# MIXR_UI.net
KiCad netlist of a schematic drawn in Altium Designer
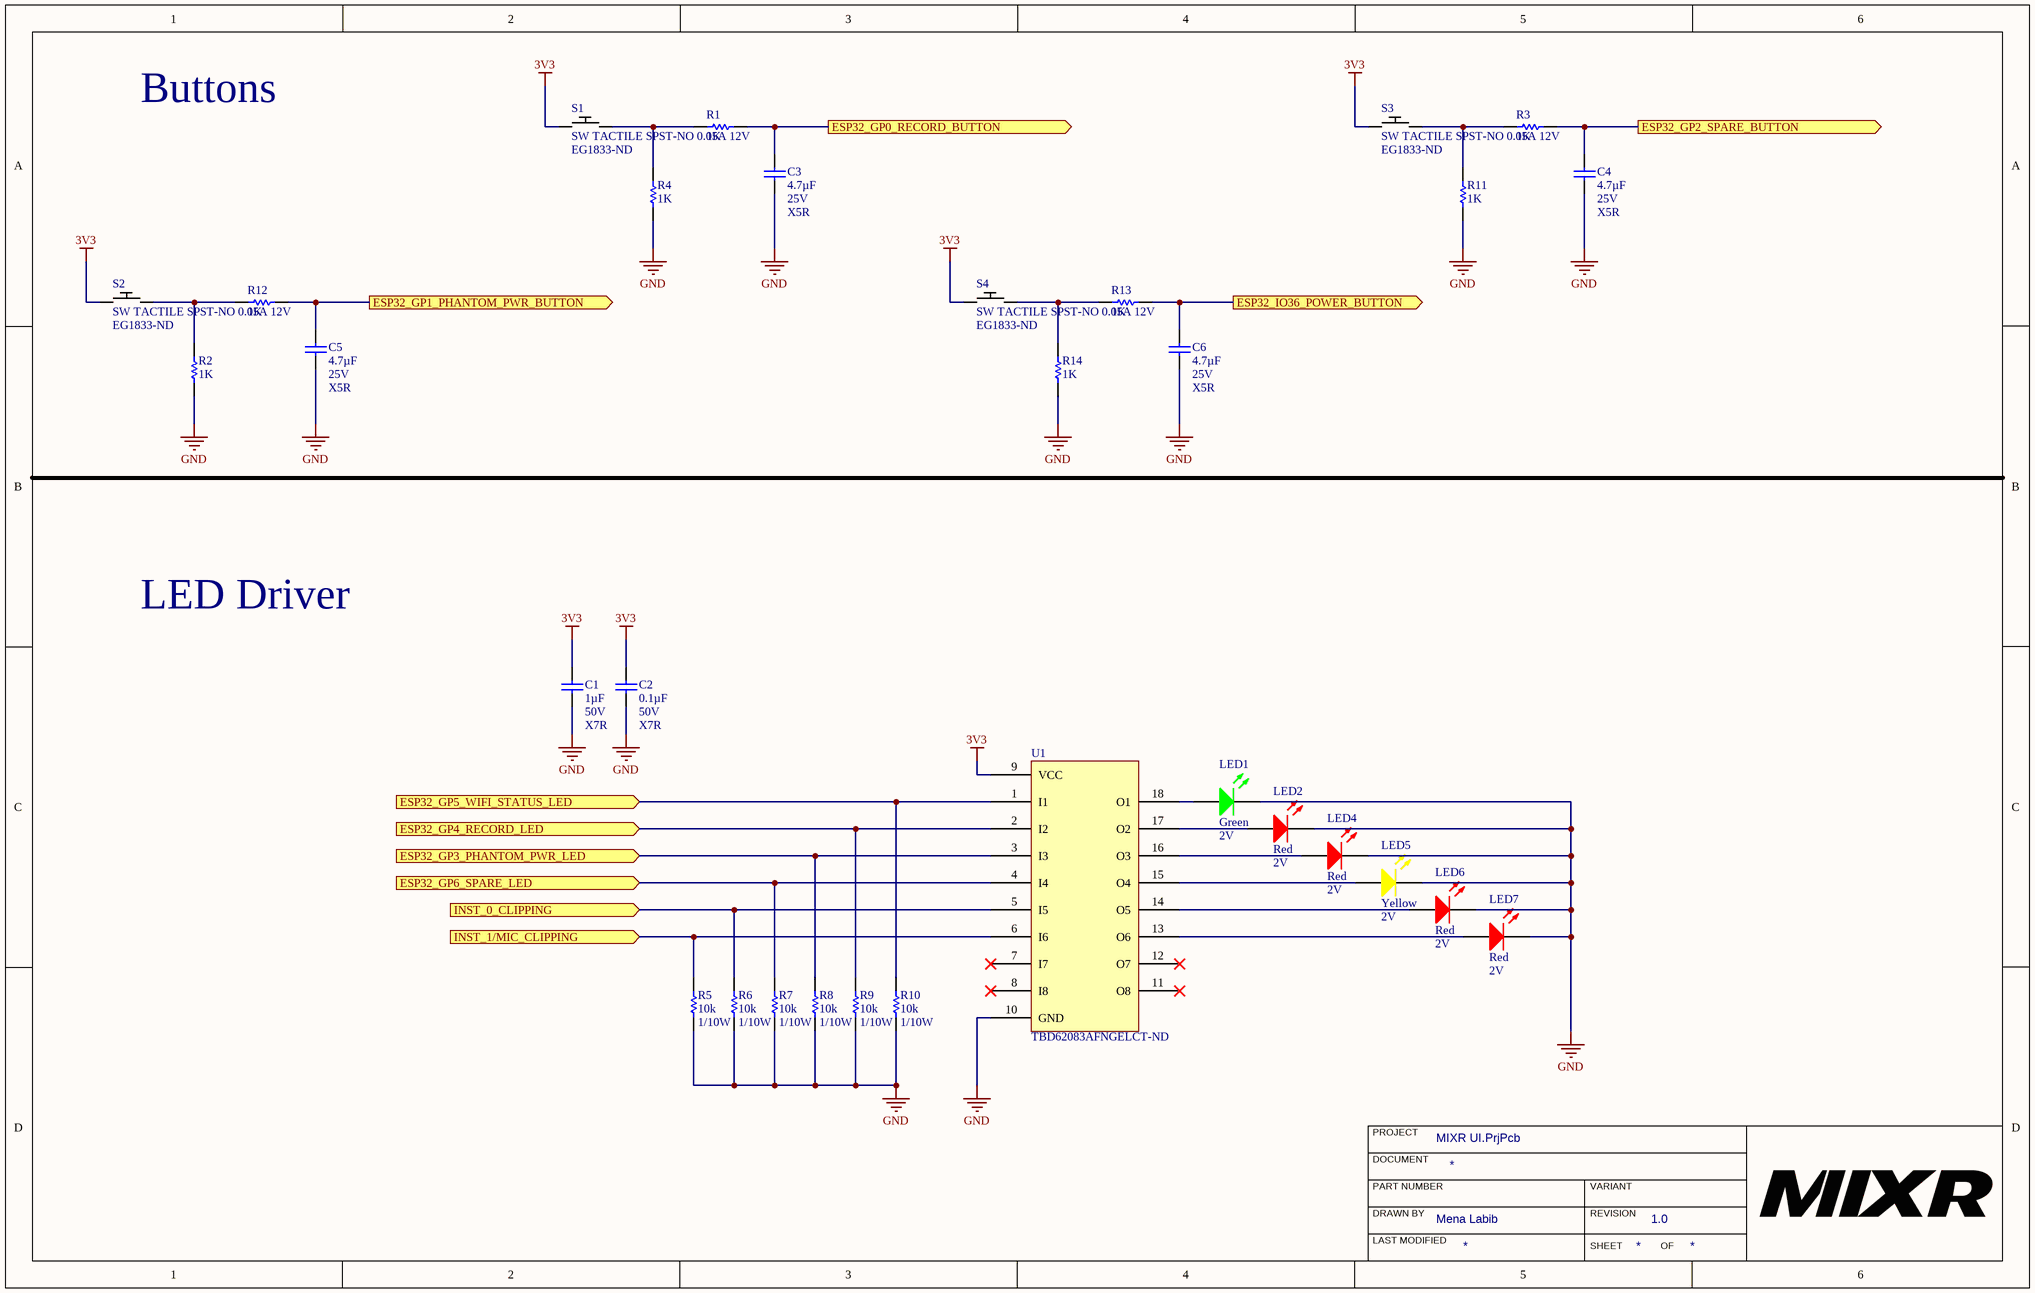
[diagram p0: MIXR UI.SchDoc]

(export (version "E")
  (design (tool "Eeschema 10.0.6"))
  (components
    (comp (ref "C1")
      (value "CAP CER 1UF 50V 10% X7R 0603")
      (footprint "CAP, 0603")
      (description "1µF ±10% 50V Ceramic Capacitor X7R 0603 (1608 Metric)")
      (fields
        (field (name "TOLERANCE") "±10%")
        (field (name "CAPACITANCE") "1µF")
        (field (name "VOLTAGE") "50V")
        (field (name "TEMPERATURE COEFFICIENT") "X7R")
      )
      (libsource (lib "altium-import") (part "root_0_CAP CER 1UF 50V 10% X7R 0603_"))
    )
    (comp (ref "C2")
      (value "CAP CER 0.1UF 50V 10% X7R 0603")
      (footprint "CAP, 0603")
      (description "0.10µF ±10% 50V Ceramic Capacitor X7R 0603 (1608 Metric)")
      (fields
        (field (name "TOLERANCE") "±10%")
        (field (name "CAPACITANCE") "0.1µF")
        (field (name "VOLTAGE") "50V")
        (field (name "TEMPERATURE COEFFICIENT") "X7R")
      )
      (libsource (lib "altium-import") (part "root_0_CAP CER 0.1UF 50V 10% X7R 0603_"))
    )
    (comp (ref "C3")
      (value "CAP CER 4.7UF 25V 10% X5R 0603")
      (footprint "CAP, 0603")
      (description "4.7µF ±10% 25V Ceramic Capacitor X5R 0603 (1608 Metric)")
      (fields
        (field (name "TOLERANCE") "±10%")
        (field (name "CAPACITANCE") "4.7µF")
        (field (name "VOLTAGE") "25V")
        (field (name "TEMPERATURE COEFFICIENT") "X5R")
      )
      (libsource (lib "altium-import") (part "root_0_CAP CER 4.7UF 25V 10% X5R 0603_"))
    )
    (comp (ref "C4")
      (value "CAP CER 4.7UF 25V 10% X5R 0603")
      (footprint "CAP, 0603")
      (description "4.7µF ±10% 25V Ceramic Capacitor X5R 0603 (1608 Metric)")
      (fields
        (field (name "TOLERANCE") "±10%")
        (field (name "CAPACITANCE") "4.7µF")
        (field (name "VOLTAGE") "25V")
        (field (name "TEMPERATURE COEFFICIENT") "X5R")
      )
      (libsource (lib "altium-import") (part "root_0_CAP CER 4.7UF 25V 10% X5R 0603_"))
    )
    (comp (ref "C5")
      (value "CAP CER 4.7UF 25V 10% X5R 0603")
      (footprint "CAP, 0603")
      (description "4.7µF ±10% 25V Ceramic Capacitor X5R 0603 (1608 Metric)")
      (fields
        (field (name "TOLERANCE") "±10%")
        (field (name "CAPACITANCE") "4.7µF")
        (field (name "VOLTAGE") "25V")
        (field (name "TEMPERATURE COEFFICIENT") "X5R")
      )
      (libsource (lib "altium-import") (part "root_0_CAP CER 4.7UF 25V 10% X5R 0603_"))
    )
    (comp (ref "C6")
      (value "CAP CER 4.7UF 25V 10% X5R 0603")
      (footprint "CAP, 0603")
      (description "4.7µF ±10% 25V Ceramic Capacitor X5R 0603 (1608 Metric)")
      (fields
        (field (name "TOLERANCE") "±10%")
        (field (name "CAPACITANCE") "4.7µF")
        (field (name "VOLTAGE") "25V")
        (field (name "TEMPERATURE COEFFICIENT") "X5R")
      )
      (libsource (lib "altium-import") (part "root_0_CAP CER 4.7UF 25V 10% X5R 0603_"))
    )
    (comp (ref "LED1")
      (value "LED GREEN CLEAR 2V 0603")
      (footprint "LED_0603")
      (description "Green 572nm LED Indication - Discrete 2V 0603 (1608 Metric)")
      (fields
        (field (name "MANUFACTURER") "Wurth Electronics Inc.")
        (field (name "MANUFACTURER PART NUMBER") "150060VS75000")
        (field (name "COLOR") "Green")
        (field (name "VOLTAGE - FORWARD (VF) (TYP)") "2V")
      )
      (libsource (lib "altium-import") (part "root_0_LED GREEN CLEAR 2V 0603_"))
    )
    (comp (ref "LED2")
      (value "LED RED CLEAR 2V 0603")
      (footprint "LED_0603")
      (description "Red 631nm LED Indication - Discrete 2V 0603 (1608 Metric)")
      (fields
        (field (name "MANUFACTURER") "Wurth Electronics Inc.")
        (field (name "MANUFACTURER PART NUMBER") "150060RS75000")
        (field (name "COLOR") "Red")
        (field (name "VOLTAGE - FORWARD (VF) (TYP)") "2V")
      )
      (libsource (lib "altium-import") (part "root_0_LED RED CLEAR 2V 0603_"))
    )
    (comp (ref "LED4")
      (value "LED RED CLEAR 2V 0603")
      (footprint "LED_0603")
      (description "Red 631nm LED Indication - Discrete 2V 0603 (1608 Metric)")
      (fields
        (field (name "MANUFACTURER") "Wurth Electronics Inc.")
        (field (name "MANUFACTURER PART NUMBER") "150060RS75000")
        (field (name "COLOR") "Red")
        (field (name "VOLTAGE - FORWARD (VF) (TYP)") "2V")
      )
      (libsource (lib "altium-import") (part "root_0_LED RED CLEAR 2V 0603_"))
    )
    (comp (ref "LED5")
      (value "LED YELLOW CLEAR 2.1V 0603")
      (footprint "LED_0603")
      (description "Yellow 590nm LED Indication - Discrete 2V 0603 (1608 Metric)")
      (fields
        (field (name "MANUFACTURER") "Wurth Electronics Inc.")
        (field (name "MANUFACTURER PART NUMBER") "150060YS75000")
        (field (name "COLOR") "Yellow")
        (field (name "VOLTAGE - FORWARD (VF) (TYP)") "2V")
      )
      (libsource (lib "altium-import") (part "root_0_LED YELLOW CLEAR 2.1V 0603_"))
    )
    (comp (ref "LED6")
      (value "LED RED CLEAR 2V 0603")
      (footprint "LED_0603")
      (description "Red 631nm LED Indication - Discrete 2V 0603 (1608 Metric)")
      (fields
        (field (name "MANUFACTURER") "Wurth Electronics Inc.")
        (field (name "MANUFACTURER PART NUMBER") "150060RS75000")
        (field (name "COLOR") "Red")
        (field (name "VOLTAGE - FORWARD (VF) (TYP)") "2V")
      )
      (libsource (lib "altium-import") (part "root_0_LED RED CLEAR 2V 0603_"))
    )
    (comp (ref "LED7")
      (value "LED RED CLEAR 2V 0603")
      (footprint "LED_0603")
      (description "Red 631nm LED Indication - Discrete 2V 0603 (1608 Metric)")
      (fields
        (field (name "MANUFACTURER") "Wurth Electronics Inc.")
        (field (name "MANUFACTURER PART NUMBER") "150060RS75000")
        (field (name "COLOR") "Red")
        (field (name "VOLTAGE - FORWARD (VF) (TYP)") "2V")
      )
      (libsource (lib "altium-import") (part "root_0_LED RED CLEAR 2V 0603_"))
    )
    (comp (ref "R1")
      (value "1K")
      (footprint "RES, 0603")
      (description "1k Ohm ±5% 0.1W, 1/10W Chip Resistor 0603 (1608 Metric)")
      (fields
        (field (name "MANUFACTURER") "Yageo")
        (field (name "MANUFACTURER PART NUMBER") "RC0603JR-071KL")
      )
      (libsource (lib "altium-import") (part "root_1_RES 1K OHM 5% 1/10W 0603_"))
    )
    (comp (ref "R2")
      (value "1K")
      (footprint "RES, 0603")
      (description "1k Ohm ±5% 0.1W, 1/10W Chip Resistor 0603 (1608 Metric)")
      (fields
        (field (name "MANUFACTURER") "Yageo")
        (field (name "MANUFACTURER PART NUMBER") "RC0603JR-071KL")
      )
      (libsource (lib "altium-import") (part "root_0_RES 1K OHM 5% 1/10W 0603_"))
    )
    (comp (ref "R3")
      (value "1K")
      (footprint "RES, 0603")
      (description "1k Ohm ±5% 0.1W, 1/10W Chip Resistor 0603 (1608 Metric)")
      (fields
        (field (name "MANUFACTURER") "Yageo")
        (field (name "MANUFACTURER PART NUMBER") "RC0603JR-071KL")
      )
      (libsource (lib "altium-import") (part "root_1_RES 1K OHM 5% 1/10W 0603_"))
    )
    (comp (ref "R4")
      (value "1K")
      (footprint "RES, 0603")
      (description "1k Ohm ±5% 0.1W, 1/10W Chip Resistor 0603 (1608 Metric)")
      (fields
        (field (name "MANUFACTURER") "Yageo")
        (field (name "MANUFACTURER PART NUMBER") "RC0603JR-071KL")
      )
      (libsource (lib "altium-import") (part "root_0_RES 1K OHM 5% 1/10W 0603_"))
    )
    (comp (ref "R5")
      (value "RES 10K OHM 1% 1/10W 0603")
      (footprint "RES, 0603")
      (description "RES SMD 10K OHM 1% 1/10W 0603")
      (fields
        (field (name "TOLERANCE") "±1%")
        (field (name "RESISTANCE") "10k")
        (field (name "POWER") "1/10W")
      )
      (libsource (lib "altium-import") (part "root_2_RES 10K OHM 1% 1/10W 0603_"))
    )
    (comp (ref "R6")
      (value "RES 10K OHM 1% 1/10W 0603")
      (footprint "RES, 0603")
      (description "RES SMD 10K OHM 1% 1/10W 0603")
      (fields
        (field (name "TOLERANCE") "±1%")
        (field (name "RESISTANCE") "10k")
        (field (name "POWER") "1/10W")
      )
      (libsource (lib "altium-import") (part "root_2_RES 10K OHM 1% 1/10W 0603_"))
    )
    (comp (ref "R7")
      (value "RES 10K OHM 1% 1/10W 0603")
      (footprint "RES, 0603")
      (description "RES SMD 10K OHM 1% 1/10W 0603")
      (fields
        (field (name "TOLERANCE") "±1%")
        (field (name "RESISTANCE") "10k")
        (field (name "POWER") "1/10W")
      )
      (libsource (lib "altium-import") (part "root_2_RES 10K OHM 1% 1/10W 0603_"))
    )
    (comp (ref "R8")
      (value "RES 10K OHM 1% 1/10W 0603")
      (footprint "RES, 0603")
      (description "RES SMD 10K OHM 1% 1/10W 0603")
      (fields
        (field (name "TOLERANCE") "±1%")
        (field (name "RESISTANCE") "10k")
        (field (name "POWER") "1/10W")
      )
      (libsource (lib "altium-import") (part "root_2_RES 10K OHM 1% 1/10W 0603_"))
    )
    (comp (ref "R9")
      (value "RES 10K OHM 1% 1/10W 0603")
      (footprint "RES, 0603")
      (description "RES SMD 10K OHM 1% 1/10W 0603")
      (fields
        (field (name "TOLERANCE") "±1%")
        (field (name "RESISTANCE") "10k")
        (field (name "POWER") "1/10W")
      )
      (libsource (lib "altium-import") (part "root_2_RES 10K OHM 1% 1/10W 0603_"))
    )
    (comp (ref "R10")
      (value "RES 10K OHM 1% 1/10W 0603")
      (footprint "RES, 0603")
      (description "RES SMD 10K OHM 1% 1/10W 0603")
      (fields
        (field (name "TOLERANCE") "±1%")
        (field (name "RESISTANCE") "10k")
        (field (name "POWER") "1/10W")
      )
      (libsource (lib "altium-import") (part "root_2_RES 10K OHM 1% 1/10W 0603_"))
    )
    (comp (ref "R11")
      (value "1K")
      (footprint "RES, 0603")
      (description "1k Ohm ±5% 0.1W, 1/10W Chip Resistor 0603 (1608 Metric)")
      (fields
        (field (name "MANUFACTURER") "Yageo")
        (field (name "MANUFACTURER PART NUMBER") "RC0603JR-071KL")
      )
      (libsource (lib "altium-import") (part "root_0_RES 1K OHM 5% 1/10W 0603_"))
    )
    (comp (ref "R12")
      (value "1K")
      (footprint "RES, 0603")
      (description "1k Ohm ±5% 0.1W, 1/10W Chip Resistor 0603 (1608 Metric)")
      (fields
        (field (name "MANUFACTURER") "Yageo")
        (field (name "MANUFACTURER PART NUMBER") "RC0603JR-071KL")
      )
      (libsource (lib "altium-import") (part "root_1_RES 1K OHM 5% 1/10W 0603_"))
    )
    (comp (ref "R13")
      (value "1K")
      (footprint "RES, 0603")
      (description "1k Ohm ±5% 0.1W, 1/10W Chip Resistor 0603 (1608 Metric)")
      (fields
        (field (name "MANUFACTURER") "Yageo")
        (field (name "MANUFACTURER PART NUMBER") "RC0603JR-071KL")
      )
      (libsource (lib "altium-import") (part "root_1_RES 1K OHM 5% 1/10W 0603_"))
    )
    (comp (ref "R14")
      (value "1K")
      (footprint "RES, 0603")
      (description "1k Ohm ±5% 0.1W, 1/10W Chip Resistor 0603 (1608 Metric)")
      (fields
        (field (name "MANUFACTURER") "Yageo")
        (field (name "MANUFACTURER PART NUMBER") "RC0603JR-071KL")
      )
      (libsource (lib "altium-import") (part "root_0_RES 1K OHM 5% 1/10W 0603_"))
    )
    (comp (ref "S1")
      (value "SW TACTILE SPST-NO 0.05A 12V")
      (footprint "SW SPST-NO 6x6mm Via Hole")
      (description "Tactile Switch SPST-NO Top Actuated Through Hole")
      (fields
        (field (name "MANUFACTURER") "E-Switch")
        (field (name "MANUFACTURER PART NUMBER") "TL1105BF160Q")
        (field (name "SUPPLIER PART NUMBER 1") "EG1833-ND")
      )
      (libsource (lib "altium-import") (part "root_0_SW TACTILE SPST-NO 0.05A 12V_"))
    )
    (comp (ref "S2")
      (value "SW TACTILE SPST-NO 0.05A 12V")
      (footprint "SW SPST-NO 6x6mm Via Hole")
      (description "Tactile Switch SPST-NO Top Actuated Through Hole")
      (fields
        (field (name "MANUFACTURER") "E-Switch")
        (field (name "MANUFACTURER PART NUMBER") "TL1105BF160Q")
        (field (name "SUPPLIER PART NUMBER 1") "EG1833-ND")
      )
      (libsource (lib "altium-import") (part "root_0_SW TACTILE SPST-NO 0.05A 12V_"))
    )
    (comp (ref "S3")
      (value "SW TACTILE SPST-NO 0.05A 12V")
      (footprint "SW SPST-NO 6x6mm Via Hole")
      (description "Tactile Switch SPST-NO Top Actuated Through Hole")
      (fields
        (field (name "MANUFACTURER") "E-Switch")
        (field (name "MANUFACTURER PART NUMBER") "TL1105BF160Q")
        (field (name "SUPPLIER PART NUMBER 1") "EG1833-ND")
      )
      (libsource (lib "altium-import") (part "root_0_SW TACTILE SPST-NO 0.05A 12V_"))
    )
    (comp (ref "S4")
      (value "SW TACTILE SPST-NO 0.05A 12V")
      (footprint "SW SPST-NO 6x6mm Via Hole")
      (description "Tactile Switch SPST-NO Top Actuated Through Hole")
      (fields
        (field (name "MANUFACTURER") "E-Switch")
        (field (name "MANUFACTURER PART NUMBER") "TL1105BF160Q")
        (field (name "SUPPLIER PART NUMBER 1") "EG1833-ND")
      )
      (libsource (lib "altium-import") (part "root_0_SW TACTILE SPST-NO 0.05A 12V_"))
    )
    (comp (ref "U1")
      (value "IC LOAD SWITCH 8CH 0.5A 18SSOP")
      (footprint "IC LOAD SWITCH 8CH 0.5A 18-SSOP")
      (description "IC LOAD SWITCH 8CHANNEL 0.5A 18SSOP")
      (fields
        (field (name "MANUFACTURER") "Toshiba")
        (field (name "MANUFACTURER PART NUMBER") "TBD62083AFNG,EL")
        (field (name "SUPPLIER PART NUMBER 1") "TBD62083AFNGELCT-ND")
      )
      (libsource (lib "altium-import") (part "root_0_IC LOAD SWITCH 8CH 0.5A 18SSOP_"))
    )
  )
  (nets
    (net (code "1") (name "/ESP32_GP0_RECORD_BUTTON") (class "Default")
      (node (ref "C3") (pin "1") (pinfunction "1_1") (pintype "passive"))
      (node (ref "R1") (pin "2") (pinfunction "2_2") (pintype "passive"))
    )
    (net (code "2") (name "/ESP32_GP1_PHANTOM_PWR_BUTTON") (class "Default")
      (node (ref "C5") (pin "1") (pinfunction "1_1") (pintype "passive"))
      (node (ref "R12") (pin "2") (pinfunction "2_2") (pintype "passive"))
    )
    (net (code "3") (name "/ESP32_GP2_SPARE_BUTTON") (class "Default")
      (node (ref "C4") (pin "1") (pinfunction "1_1") (pintype "passive"))
      (node (ref "R3") (pin "2") (pinfunction "2_2") (pintype "passive"))
    )
    (net (code "4") (name "/ESP32_GP3_PHANTOM_PWR_LED") (class "Default")
      (node (ref "R8") (pin "2") (pinfunction "2_2") (pintype "passive"))
      (node (ref "U1") (pin "3") (pinfunction "I3_3") (pintype "passive"))
    )
    (net (code "5") (name "/ESP32_GP4_RECORD_LED") (class "Default")
      (node (ref "R9") (pin "2") (pinfunction "2_2") (pintype "passive"))
      (node (ref "U1") (pin "2") (pinfunction "I2_2") (pintype "passive"))
    )
    (net (code "6") (name "/ESP32_GP5_WIFI_STATUS_LED") (class "Default")
      (node (ref "R10") (pin "2") (pinfunction "2_2") (pintype "passive"))
      (node (ref "U1") (pin "1") (pinfunction "I1_1") (pintype "passive"))
    )
    (net (code "7") (name "/ESP32_GP6_SPARE_LED") (class "Default")
      (node (ref "R7") (pin "2") (pinfunction "2_2") (pintype "passive"))
      (node (ref "U1") (pin "4") (pinfunction "I4_4") (pintype "passive"))
    )
    (net (code "8") (name "/ESP32_IO36_POWER_BUTTON") (class "Default")
      (node (ref "C6") (pin "1") (pinfunction "1_1") (pintype "passive"))
      (node (ref "R13") (pin "2") (pinfunction "2_2") (pintype "passive"))
    )
    (net (code "9") (name "/INST_0_CLIPPING") (class "Default")
      (node (ref "R6") (pin "2") (pinfunction "2_2") (pintype "passive"))
      (node (ref "U1") (pin "5") (pinfunction "I5_5") (pintype "passive"))
    )
    (net (code "10") (name "/INST_1{slash}MIC_CLIPPING") (class "Default")
      (node (ref "R5") (pin "2") (pinfunction "2_2") (pintype "passive"))
      (node (ref "U1") (pin "6") (pinfunction "I6_6") (pintype "passive"))
    )
    (net (code "11") (name "3V3") (class "Default")
      (node (ref "C1") (pin "1") (pinfunction "1_1") (pintype "passive"))
      (node (ref "C2") (pin "1") (pinfunction "1_1") (pintype "passive"))
      (node (ref "S1") (pin "1") (pinfunction "1_1") (pintype "passive"))
      (node (ref "S2") (pin "1") (pinfunction "1_1") (pintype "passive"))
      (node (ref "S3") (pin "1") (pinfunction "1_1") (pintype "passive"))
      (node (ref "S4") (pin "1") (pinfunction "1_1") (pintype "passive"))
      (node (ref "U1") (pin "9") (pinfunction "VCC_9") (pintype "passive"))
    )
    (net (code "12") (name "GND") (class "Default")
      (node (ref "C1") (pin "2") (pinfunction "2_2") (pintype "passive"))
      (node (ref "C2") (pin "2") (pinfunction "2_2") (pintype "passive"))
      (node (ref "C3") (pin "2") (pinfunction "2_2") (pintype "passive"))
      (node (ref "C4") (pin "2") (pinfunction "2_2") (pintype "passive"))
      (node (ref "C5") (pin "2") (pinfunction "2_2") (pintype "passive"))
      (node (ref "C6") (pin "2") (pinfunction "2_2") (pintype "passive"))
      (node (ref "LED1") (pin "2") (pinfunction "K_2") (pintype "passive"))
      (node (ref "LED2") (pin "2") (pinfunction "K_2") (pintype "passive"))
      (node (ref "LED4") (pin "2") (pinfunction "K_2") (pintype "passive"))
      (node (ref "LED5") (pin "2") (pinfunction "K_2") (pintype "passive"))
      (node (ref "LED6") (pin "2") (pinfunction "K_2") (pintype "passive"))
      (node (ref "LED7") (pin "2") (pinfunction "K_2") (pintype "passive"))
      (node (ref "R10") (pin "1") (pinfunction "1_1") (pintype "passive"))
      (node (ref "R11") (pin "2") (pinfunction "2_2") (pintype "passive"))
      (node (ref "R14") (pin "2") (pinfunction "2_2") (pintype "passive"))
      (node (ref "R2") (pin "2") (pinfunction "2_2") (pintype "passive"))
      (node (ref "R4") (pin "2") (pinfunction "2_2") (pintype "passive"))
      (node (ref "R5") (pin "1") (pinfunction "1_1") (pintype "passive"))
      (node (ref "R6") (pin "1") (pinfunction "1_1") (pintype "passive"))
      (node (ref "R7") (pin "1") (pinfunction "1_1") (pintype "passive"))
      (node (ref "R8") (pin "1") (pinfunction "1_1") (pintype "passive"))
      (node (ref "R9") (pin "1") (pinfunction "1_1") (pintype "passive"))
      (node (ref "U1") (pin "10") (pinfunction "GND_10") (pintype "passive"))
    )
    (net (code "13") (name "Net-(LED1-A)") (class "Default")
      (node (ref "LED1") (pin "1") (pinfunction "A_1") (pintype "passive"))
      (node (ref "U1") (pin "18") (pinfunction "O1_18") (pintype "passive"))
    )
    (net (code "14") (name "Net-(LED2-A)") (class "Default")
      (node (ref "LED2") (pin "1") (pinfunction "A_1") (pintype "passive"))
      (node (ref "U1") (pin "17") (pinfunction "O2_17") (pintype "passive"))
    )
    (net (code "15") (name "Net-(LED4-A)") (class "Default")
      (node (ref "LED4") (pin "1") (pinfunction "A_1") (pintype "passive"))
      (node (ref "U1") (pin "16") (pinfunction "O3_16") (pintype "passive"))
    )
    (net (code "16") (name "Net-(LED5-A)") (class "Default")
      (node (ref "LED5") (pin "1") (pinfunction "A_1") (pintype "passive"))
      (node (ref "U1") (pin "15") (pinfunction "O4_15") (pintype "passive"))
    )
    (net (code "17") (name "Net-(LED6-A)") (class "Default")
      (node (ref "LED6") (pin "1") (pinfunction "A_1") (pintype "passive"))
      (node (ref "U1") (pin "14") (pinfunction "O5_14") (pintype "passive"))
    )
    (net (code "18") (name "Net-(LED7-A)") (class "Default")
      (node (ref "LED7") (pin "1") (pinfunction "A_1") (pintype "passive"))
      (node (ref "U1") (pin "13") (pinfunction "O6_13") (pintype "passive"))
    )
    (net (code "19") (name "Net-(R1-Pad1)") (class "Default")
      (node (ref "R1") (pin "1") (pinfunction "1_1") (pintype "passive"))
      (node (ref "R4") (pin "1") (pinfunction "1_1") (pintype "passive"))
      (node (ref "S1") (pin "2") (pinfunction "2_2") (pintype "passive"))
    )
    (net (code "20") (name "Net-(R11-Pad1)") (class "Default")
      (node (ref "R11") (pin "1") (pinfunction "1_1") (pintype "passive"))
      (node (ref "R3") (pin "1") (pinfunction "1_1") (pintype "passive"))
      (node (ref "S3") (pin "2") (pinfunction "2_2") (pintype "passive"))
    )
    (net (code "21") (name "Net-(R12-Pad1)") (class "Default")
      (node (ref "R12") (pin "1") (pinfunction "1_1") (pintype "passive"))
      (node (ref "R2") (pin "1") (pinfunction "1_1") (pintype "passive"))
      (node (ref "S2") (pin "2") (pinfunction "2_2") (pintype "passive"))
    )
    (net (code "22") (name "Net-(R13-Pad1)") (class "Default")
      (node (ref "R13") (pin "1") (pinfunction "1_1") (pintype "passive"))
      (node (ref "R14") (pin "1") (pinfunction "1_1") (pintype "passive"))
      (node (ref "S4") (pin "2") (pinfunction "2_2") (pintype "passive"))
    )
    (net (code "23") (name "unconnected-(U1-I7-Pad7)") (class "Default")
      (node (ref "U1") (pin "7") (pinfunction "I7_7") (pintype "passive+no_connect"))
    )
    (net (code "24") (name "unconnected-(U1-I8-Pad8)") (class "Default")
      (node (ref "U1") (pin "8") (pinfunction "I8_8") (pintype "passive+no_connect"))
    )
    (net (code "25") (name "unconnected-(U1-O7-Pad12)") (class "Default")
      (node (ref "U1") (pin "12") (pinfunction "O7_12") (pintype "passive+no_connect"))
    )
    (net (code "26") (name "unconnected-(U1-O8-Pad11)") (class "Default")
      (node (ref "U1") (pin "11") (pinfunction "O8_11") (pintype "passive+no_connect"))
    )
  )
)
